# single_supply_control_V13_SD4.net
KiCad netlist of a schematic drawn in EAGLE
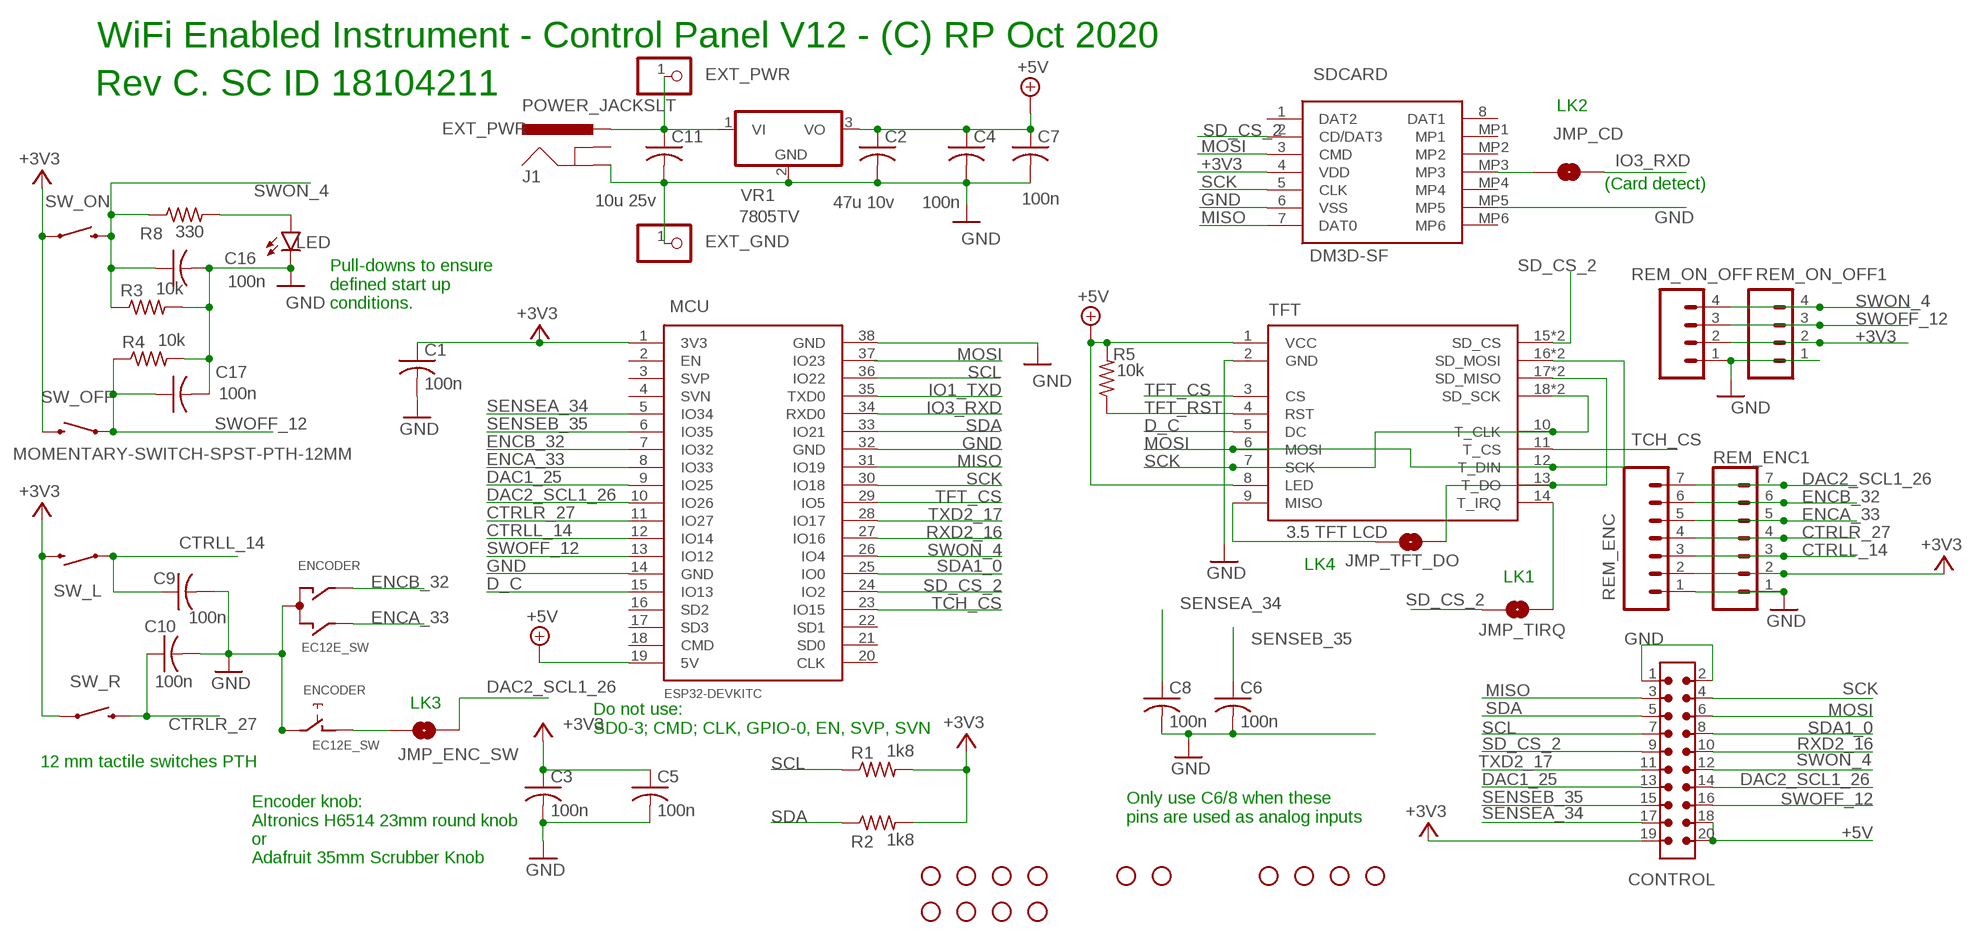
[diagram p0: schematic, sheet 1]

(export (version "E")
  (design (tool "Eeschema 10.0.6"))
  (components
    (comp (ref "C1")
      (value "100n")
      (footprint "eagle-import:C0805K")
      (libsource (lib "eagle-import") (part "C-USC0805K"))
    )
    (comp (ref "C2")
      (value "47u 10v")
      (footprint "eagle-import:C1210K")
      (libsource (lib "eagle-import") (part "C-USC1210K"))
    )
    (comp (ref "C3")
      (value "100n")
      (footprint "eagle-import:C0805K")
      (libsource (lib "eagle-import") (part "C-USC0805K"))
    )
    (comp (ref "C4")
      (value "100n")
      (footprint "eagle-import:C0805K")
      (libsource (lib "eagle-import") (part "C-USC0805K"))
    )
    (comp (ref "C5")
      (value "100n")
      (footprint "eagle-import:C0805K")
      (libsource (lib "eagle-import") (part "C-USC0805K"))
    )
    (comp (ref "C6")
      (value "100n")
      (footprint "eagle-import:C0805K")
      (libsource (lib "eagle-import") (part "C-USC0805K"))
    )
    (comp (ref "C7")
      (value "100n")
      (footprint "eagle-import:C0805K")
      (libsource (lib "eagle-import") (part "C-USC0805K"))
    )
    (comp (ref "C8")
      (value "100n")
      (footprint "eagle-import:C0805K")
      (libsource (lib "eagle-import") (part "C-USC0805K"))
    )
    (comp (ref "C9")
      (value "100n")
      (footprint "eagle-import:C0805K")
      (libsource (lib "eagle-import") (part "C-USC0805K"))
    )
    (comp (ref "C10")
      (value "100n")
      (footprint "eagle-import:C0805K")
      (libsource (lib "eagle-import") (part "C-USC0805K"))
    )
    (comp (ref "C11")
      (value "10u 25v")
      (footprint "eagle-import:C1210K")
      (libsource (lib "eagle-import") (part "C-USC1210K"))
    )
    (comp (ref "C16")
      (value "100n")
      (footprint "eagle-import:C0805K")
      (libsource (lib "eagle-import") (part "C-USC0805K"))
    )
    (comp (ref "C17")
      (value "100n")
      (footprint "eagle-import:C0805K")
      (libsource (lib "eagle-import") (part "C-USC0805K"))
    )
    (comp (ref "CONTROL")
      (value "6120XX21621_61202021621")
      (footprint "eagle-import:61202021621")
      (libsource (lib "eagle-import") (part "6120XX21621_61202021621"))
    )
    (comp (ref "ENCODER")
      (value "EC12E_SW")
      (footprint "eagle-import:ALPS_EC12E_SW")
      (fields (field (name "MPN") "EC12E2424407"))
      (libsource (lib "eagle-import") (part "EC12E_SW"))
    )
    (comp (ref "EXT_GND")
      (value "PINHD-1X1")
      (footprint "eagle-import:1X01")
      (libsource (lib "eagle-import") (part "PINHD-1X1"))
    )
    (comp (ref "EXT_PWR")
      (value "PINHD-1X1")
      (footprint "eagle-import:1X01")
      (libsource (lib "eagle-import") (part "PINHD-1X1"))
    )
    (comp (ref "H1")
      (value "STAND-OFF")
      (footprint "eagle-import:STAND-OFF")
      (libsource (lib "eagle-import") (part "STAND-OFF"))
    )
    (comp (ref "H2")
      (value "STAND-OFF")
      (footprint "eagle-import:STAND-OFF")
      (libsource (lib "eagle-import") (part "STAND-OFF"))
    )
    (comp (ref "H3")
      (value "STAND-OFF")
      (footprint "eagle-import:STAND-OFF")
      (libsource (lib "eagle-import") (part "STAND-OFF"))
    )
    (comp (ref "H4")
      (value "STAND-OFF")
      (footprint "eagle-import:STAND-OFF")
      (libsource (lib "eagle-import") (part "STAND-OFF"))
    )
    (comp (ref "H5")
      (value "STAND-OFF")
      (footprint "eagle-import:STAND-OFF")
      (libsource (lib "eagle-import") (part "STAND-OFF"))
    )
    (comp (ref "H6")
      (value "STAND-OFF")
      (footprint "eagle-import:STAND-OFF")
      (libsource (lib "eagle-import") (part "STAND-OFF"))
    )
    (comp (ref "H7")
      (value "STAND-OFF")
      (footprint "eagle-import:STAND-OFF")
      (libsource (lib "eagle-import") (part "STAND-OFF"))
    )
    (comp (ref "H8")
      (value "STAND-OFF")
      (footprint "eagle-import:STAND-OFF")
      (libsource (lib "eagle-import") (part "STAND-OFF"))
    )
    (comp (ref "H9")
      (value "STAND-OFF")
      (footprint "eagle-import:STAND-OFF")
      (libsource (lib "eagle-import") (part "STAND-OFF"))
    )
    (comp (ref "H10")
      (value "STAND-OFF")
      (footprint "eagle-import:STAND-OFF")
      (libsource (lib "eagle-import") (part "STAND-OFF"))
    )
    (comp (ref "H11")
      (value "STAND-OFF")
      (footprint "eagle-import:STAND-OFF")
      (libsource (lib "eagle-import") (part "STAND-OFF"))
    )
    (comp (ref "H12")
      (value "STAND-OFF")
      (footprint "eagle-import:STAND-OFF")
      (libsource (lib "eagle-import") (part "STAND-OFF"))
    )
    (comp (ref "H13")
      (value "STAND-OFF")
      (footprint "eagle-import:STAND-OFF")
      (libsource (lib "eagle-import") (part "STAND-OFF"))
    )
    (comp (ref "H14")
      (value "STAND-OFF")
      (footprint "eagle-import:STAND-OFF")
      (libsource (lib "eagle-import") (part "STAND-OFF"))
    )
    (comp (ref "J1")
      (value "POWER_JACKSLT")
      (footprint "eagle-import:POWER_JACK_SLOT")
      (libsource (lib "eagle-import") (part "POWER_JACKSLT"))
    )
    (comp (ref "JMP_CD")
      (value "JUMPER-SMT_2_NO_SILK")
      (footprint "eagle-import:SMT-JUMPER_2_NO_SILK")
      (libsource (lib "eagle-import") (part "JUMPER-SMT_2_NO_SILK"))
    )
    (comp (ref "JMP_ENC_SW")
      (value "JUMPER-SMT_2_NO_SILK")
      (footprint "eagle-import:SMT-JUMPER_2_NO_SILK")
      (libsource (lib "eagle-import") (part "JUMPER-SMT_2_NO_SILK"))
    )
    (comp (ref "JMP_TFT_DO")
      (value "JUMPER-SMT_2_NO_SILK")
      (footprint "eagle-import:SMT-JUMPER_2_NO_SILK")
      (libsource (lib "eagle-import") (part "JUMPER-SMT_2_NO_SILK"))
    )
    (comp (ref "JMP_TIRQ")
      (value "JUMPER-SMT_2_NO_SILK")
      (footprint "eagle-import:SMT-JUMPER_2_NO_SILK")
      (libsource (lib "eagle-import") (part "JUMPER-SMT_2_NO_SILK"))
    )
    (comp (ref "LED")
      (value "LED3MM")
      (footprint "eagle-import:LED_3MM")
      (libsource (lib "eagle-import") (part "LED3MM"))
    )
    (comp (ref "MCU")
      (value "ESP32DEVKITC")
      (footprint "eagle-import:ESP32-DEVKITC")
      (libsource (lib "eagle-import") (part "ESP32DEVKITC"))
    )
    (comp (ref "R1")
      (value "1k8")
      (footprint "eagle-import:R0805W")
      (libsource (lib "eagle-import") (part "R-US_R0805W"))
    )
    (comp (ref "R2")
      (value "1k8")
      (footprint "eagle-import:R0805W")
      (libsource (lib "eagle-import") (part "R-US_R0805W"))
    )
    (comp (ref "R3")
      (value "10k")
      (footprint "eagle-import:R0805W")
      (libsource (lib "eagle-import") (part "R-US_R0805W"))
    )
    (comp (ref "R4")
      (value "10k")
      (footprint "eagle-import:R0805W")
      (libsource (lib "eagle-import") (part "R-US_R0805W"))
    )
    (comp (ref "R5")
      (value "10k")
      (footprint "eagle-import:R0805W")
      (libsource (lib "eagle-import") (part "R-US_R0805W"))
    )
    (comp (ref "R8")
      (value "330")
      (footprint "eagle-import:R0805W")
      (libsource (lib "eagle-import") (part "R-US_R0805W"))
    )
    (comp (ref "REM_ENC")
      (value "CONN_07")
      (footprint "eagle-import:1X07")
      (libsource (lib "eagle-import") (part "CONN_07"))
    )
    (comp (ref "REM_ENC1")
      (value "CONN_07")
      (footprint "eagle-import:1X07")
      (libsource (lib "eagle-import") (part "CONN_07"))
    )
    (comp (ref "REM_ON_OFF")
      (value "CONN_04")
      (footprint "eagle-import:1X04")
      (libsource (lib "eagle-import") (part "CONN_04"))
    )
    (comp (ref "REM_ON_OFF1")
      (value "CONN_04")
      (footprint "eagle-import:1X04")
      (libsource (lib "eagle-import") (part "CONN_04"))
    )
    (comp (ref "SDCARD")
      (value "DM3D-SF")
      (footprint "eagle-import:DM3DSF")
      (fields (field (name "MOUSER_PART_NUMBER") "798-DM3D-SF"))
      (libsource (lib "eagle-import") (part "DM3D-SF"))
    )
    (comp (ref "SW_L")
      (value "MOMENTARY-SWITCH-SPST-PTH-12MM")
      (footprint "eagle-import:TACTILE_SWITCH_PTH_12MM")
      (libsource (lib "eagle-import") (part "MOMENTARY-SWITCH-SPST-PTH-12MM"))
    )
    (comp (ref "SW_OFF")
      (value "MOMENTARY-SWITCH-SPST-PTH-12MM")
      (footprint "eagle-import:TACTILE_SWITCH_PTH_12MM")
      (libsource (lib "eagle-import") (part "MOMENTARY-SWITCH-SPST-PTH-12MM"))
    )
    (comp (ref "SW_ON")
      (value "MOMENTARY-SWITCH-SPST-PTH-12MM")
      (footprint "eagle-import:TACTILE_SWITCH_PTH_12MM")
      (libsource (lib "eagle-import") (part "MOMENTARY-SWITCH-SPST-PTH-12MM"))
    )
    (comp (ref "SW_R")
      (value "MOMENTARY-SWITCH-SPST-PTH-12MM")
      (footprint "eagle-import:TACTILE_SWITCH_PTH_12MM")
      (libsource (lib "eagle-import") (part "MOMENTARY-SWITCH-SPST-PTH-12MM"))
    )
    (comp (ref "TFT")
      (value "2.8_3.5_TFT_TOUCH")
      (footprint "eagle-import:2.8_3.5_TFT_LCD")
      (libsource (lib "eagle-import") (part "2.8_3.5_TFT_TOUCH"))
    )
    (comp (ref "VR1")
      (value "7805TV")
      (footprint "eagle-import:TO220V")
      (libsource (lib "eagle-import") (part "78TV05"))
    )
  )
  (nets
    (net (code "1") (name "+3V3") (class "Default")
      (node (ref "C1") (pin "1") (pinfunction "1_1") (pintype "passive"))
      (node (ref "C3") (pin "1") (pinfunction "1_1") (pintype "passive"))
      (node (ref "C5") (pin "1") (pinfunction "1_1") (pintype "passive"))
      (node (ref "CONTROL") (pin "19") (pinfunction "19_19") (pintype "passive"))
      (node (ref "MCU") (pin "1") (pinfunction "3V3_1") (pintype "bidirectional"))
      (node (ref "R1") (pin "2") (pinfunction "2_2") (pintype "passive"))
      (node (ref "R2") (pin "2") (pinfunction "2_2") (pintype "passive"))
      (node (ref "REM_ENC") (pin "2") (pinfunction "2_2") (pintype "passive"))
      (node (ref "REM_ENC1") (pin "2") (pinfunction "2_2") (pintype "passive"))
      (node (ref "REM_ON_OFF") (pin "2") (pinfunction "2_2") (pintype "passive"))
      (node (ref "REM_ON_OFF1") (pin "2") (pinfunction "2_2") (pintype "passive"))
      (node (ref "SDCARD") (pin "4") (pinfunction "VDD_4") (pintype "bidirectional"))
      (node (ref "SW_L") (pin "3") (pinfunction "2_3") (pintype "passive"))
      (node (ref "SW_OFF") (pin "3") (pinfunction "2_3") (pintype "passive"))
      (node (ref "SW_ON") (pin "1") (pinfunction "1_1") (pintype "passive"))
      (node (ref "SW_R") (pin "1") (pinfunction "1_1") (pintype "passive"))
    )
    (net (code "2") (name "+5V") (class "Default")
      (node (ref "C2") (pin "1") (pinfunction "1_1") (pintype "passive"))
      (node (ref "C4") (pin "1") (pinfunction "1_1") (pintype "passive"))
      (node (ref "C7") (pin "1") (pinfunction "1_1") (pintype "passive"))
      (node (ref "CONTROL") (pin "18") (pinfunction "18_18") (pintype "passive"))
      (node (ref "CONTROL") (pin "20") (pinfunction "20_20") (pintype "passive"))
      (node (ref "MCU") (pin "19") (pinfunction "5V_19") (pintype "bidirectional"))
      (node (ref "R5") (pin "2") (pinfunction "2_2") (pintype "passive"))
      (node (ref "TFT") (pin "1") (pinfunction "VCC_1") (pintype "power_in"))
      (node (ref "TFT") (pin "8") (pinfunction "LED_8") (pintype "bidirectional"))
      (node (ref "VR1") (pin "3") (pinfunction "VO_3") (pintype "passive"))
    )
    (net (code "3") (name "/CTRLL_14") (class "Default")
      (node (ref "C9") (pin "1") (pinfunction "1_1") (pintype "passive"))
      (node (ref "MCU") (pin "12") (pinfunction "IO14_12") (pintype "bidirectional"))
      (node (ref "REM_ENC") (pin "3") (pinfunction "3_3") (pintype "passive"))
      (node (ref "REM_ENC1") (pin "3") (pinfunction "3_3") (pintype "passive"))
      (node (ref "SW_L") (pin "1") (pinfunction "1_1") (pintype "passive"))
    )
    (net (code "4") (name "/CTRLR_27") (class "Default")
      (node (ref "C10") (pin "1") (pinfunction "1_1") (pintype "passive"))
      (node (ref "MCU") (pin "11") (pinfunction "IO27_11") (pintype "bidirectional"))
      (node (ref "REM_ENC") (pin "4") (pinfunction "4_4") (pintype "passive"))
      (node (ref "REM_ENC1") (pin "4") (pinfunction "4_4") (pintype "passive"))
      (node (ref "SW_R") (pin "3") (pinfunction "2_3") (pintype "passive"))
    )
    (net (code "5") (name "/DAC1_25") (class "Default")
      (node (ref "CONTROL") (pin "13") (pinfunction "13_13") (pintype "passive"))
      (node (ref "MCU") (pin "9") (pinfunction "IO25_9") (pintype "bidirectional"))
    )
    (net (code "6") (name "/DAC2_SCL1_26") (class "Default")
      (node (ref "CONTROL") (pin "14") (pinfunction "14_14") (pintype "passive"))
      (node (ref "JMP_ENC_SW") (pin "2") (pinfunction "2_2") (pintype "passive"))
      (node (ref "MCU") (pin "10") (pinfunction "IO26_10") (pintype "bidirectional"))
      (node (ref "REM_ENC") (pin "7") (pinfunction "7_7") (pintype "passive"))
      (node (ref "REM_ENC1") (pin "7") (pinfunction "7_7") (pintype "passive"))
    )
    (net (code "7") (name "/D_C") (class "Default")
      (node (ref "MCU") (pin "15") (pinfunction "IO13_15") (pintype "bidirectional"))
      (node (ref "TFT") (pin "5") (pinfunction "DC_5") (pintype "bidirectional"))
    )
    (net (code "8") (name "/ENCA_33") (class "Default")
      (node (ref "ENCODER") (pin "B") (pinfunction "B_B") (pintype "passive"))
      (node (ref "MCU") (pin "8") (pinfunction "IO33_8") (pintype "bidirectional"))
      (node (ref "REM_ENC") (pin "5") (pinfunction "5_5") (pintype "passive"))
      (node (ref "REM_ENC1") (pin "5") (pinfunction "5_5") (pintype "passive"))
    )
    (net (code "9") (name "/ENCB_32") (class "Default")
      (node (ref "ENCODER") (pin "A") (pinfunction "A_A") (pintype "passive"))
      (node (ref "MCU") (pin "7") (pinfunction "IO32_7") (pintype "bidirectional"))
      (node (ref "REM_ENC") (pin "6") (pinfunction "6_6") (pintype "passive"))
      (node (ref "REM_ENC1") (pin "6") (pinfunction "6_6") (pintype "passive"))
    )
    (net (code "10") (name "/EXT_PWR") (class "Default")
      (node (ref "C11") (pin "1") (pinfunction "1_1") (pintype "passive"))
      (node (ref "EXT_PWR") (pin "1") (pinfunction "1_1") (pintype "passive"))
      (node (ref "J1") (pin "PWR") (pinfunction "PWR_PWR") (pintype "bidirectional"))
      (node (ref "VR1") (pin "1") (pinfunction "VI_1") (pintype "input"))
    )
    (net (code "11") (name "/IO1_TXD") (class "Default")
      (node (ref "MCU") (pin "35") (pinfunction "TXD0_35") (pintype "bidirectional"))
    )
    (net (code "12") (name "/IO3_RXD") (class "Default")
      (node (ref "JMP_CD") (pin "2") (pinfunction "2_2") (pintype "passive"))
      (node (ref "MCU") (pin "34") (pinfunction "RXD0_34") (pintype "bidirectional"))
    )
    (net (code "13") (name "/MISO") (class "Default")
      (node (ref "CONTROL") (pin "3") (pinfunction "3_3") (pintype "passive"))
      (node (ref "JMP_TFT_DO") (pin "2") (pinfunction "2_2") (pintype "passive"))
      (node (ref "MCU") (pin "31") (pinfunction "IO19_31") (pintype "bidirectional"))
      (node (ref "SDCARD") (pin "7") (pinfunction "DAT0_7") (pintype "bidirectional"))
      (node (ref "TFT") (pin "13") (pinfunction "T_DO_13") (pintype "bidirectional"))
      (node (ref "TFT") (pin "17") (pinfunction "SD_MISO_17") (pintype "bidirectional"))
      (node (ref "TFT") (pin "30") (pinfunction "SD_MISO_30") (pintype "bidirectional"))
    )
    (net (code "14") (name "/MOSI") (class "Default")
      (node (ref "CONTROL") (pin "6") (pinfunction "6_6") (pintype "passive"))
      (node (ref "MCU") (pin "37") (pinfunction "IO23_37") (pintype "bidirectional"))
      (node (ref "SDCARD") (pin "3") (pinfunction "CMD_3") (pintype "bidirectional"))
      (node (ref "TFT") (pin "12") (pinfunction "T_DIN_12") (pintype "bidirectional"))
      (node (ref "TFT") (pin "16") (pinfunction "SD_MOSI_16") (pintype "bidirectional"))
      (node (ref "TFT") (pin "29") (pinfunction "SD_MOSI_29") (pintype "bidirectional"))
      (node (ref "TFT") (pin "6") (pinfunction "MOSI_6") (pintype "bidirectional"))
    )
    (net (code "15") (name "/RXD2_16") (class "Default")
      (node (ref "CONTROL") (pin "10") (pinfunction "10_10") (pintype "passive"))
      (node (ref "MCU") (pin "27") (pinfunction "IO16_27") (pintype "bidirectional"))
    )
    (net (code "16") (name "/SCK") (class "Default")
      (node (ref "CONTROL") (pin "4") (pinfunction "4_4") (pintype "passive"))
      (node (ref "MCU") (pin "30") (pinfunction "IO18_30") (pintype "bidirectional"))
      (node (ref "SDCARD") (pin "5") (pinfunction "CLK_5") (pintype "bidirectional"))
      (node (ref "TFT") (pin "10") (pinfunction "T_CLK_10") (pintype "bidirectional"))
      (node (ref "TFT") (pin "18") (pinfunction "SD_SCK_18") (pintype "bidirectional"))
      (node (ref "TFT") (pin "31") (pinfunction "SD_SCK_31") (pintype "bidirectional"))
      (node (ref "TFT") (pin "7") (pinfunction "SCK_7") (pintype "bidirectional"))
    )
    (net (code "17") (name "/SCL") (class "Default")
      (node (ref "CONTROL") (pin "7") (pinfunction "7_7") (pintype "passive"))
      (node (ref "MCU") (pin "36") (pinfunction "IO22_36") (pintype "bidirectional"))
      (node (ref "R1") (pin "1") (pinfunction "1_1") (pintype "passive"))
    )
    (net (code "18") (name "/SDA") (class "Default")
      (node (ref "CONTROL") (pin "5") (pinfunction "5_5") (pintype "passive"))
      (node (ref "MCU") (pin "33") (pinfunction "IO21_33") (pintype "bidirectional"))
      (node (ref "R2") (pin "1") (pinfunction "1_1") (pintype "passive"))
    )
    (net (code "19") (name "/SDA1_0") (class "Default")
      (node (ref "CONTROL") (pin "8") (pinfunction "8_8") (pintype "passive"))
      (node (ref "MCU") (pin "25") (pinfunction "IO0_25") (pintype "bidirectional"))
    )
    (net (code "20") (name "/SD_CS_2") (class "Default")
      (node (ref "CONTROL") (pin "9") (pinfunction "9_9") (pintype "passive"))
      (node (ref "JMP_TIRQ") (pin "1") (pinfunction "1_1") (pintype "passive"))
      (node (ref "MCU") (pin "24") (pinfunction "IO2_24") (pintype "bidirectional"))
      (node (ref "SDCARD") (pin "2") (pinfunction "CD/DAT3_2") (pintype "bidirectional"))
      (node (ref "TFT") (pin "15") (pinfunction "SD_CS_15") (pintype "bidirectional"))
      (node (ref "TFT") (pin "28") (pinfunction "SD_CS_28") (pintype "bidirectional"))
    )
    (net (code "21") (name "/SENSEA_34") (class "Default")
      (node (ref "C8") (pin "1") (pinfunction "1_1") (pintype "passive"))
      (node (ref "CONTROL") (pin "17") (pinfunction "17_17") (pintype "passive"))
      (node (ref "MCU") (pin "5") (pinfunction "IO34_5") (pintype "bidirectional"))
    )
    (net (code "22") (name "/SENSEB_35") (class "Default")
      (node (ref "C6") (pin "1") (pinfunction "1_1") (pintype "passive"))
      (node (ref "CONTROL") (pin "15") (pinfunction "15_15") (pintype "passive"))
      (node (ref "MCU") (pin "6") (pinfunction "IO35_6") (pintype "bidirectional"))
    )
    (net (code "23") (name "/SWOFF_12") (class "Default")
      (node (ref "C17") (pin "1") (pinfunction "1_1") (pintype "passive"))
      (node (ref "CONTROL") (pin "16") (pinfunction "16_16") (pintype "passive"))
      (node (ref "MCU") (pin "13") (pinfunction "IO12_13") (pintype "bidirectional"))
      (node (ref "R4") (pin "1") (pinfunction "1_1") (pintype "passive"))
      (node (ref "REM_ON_OFF") (pin "3") (pinfunction "3_3") (pintype "passive"))
      (node (ref "REM_ON_OFF1") (pin "3") (pinfunction "3_3") (pintype "passive"))
      (node (ref "SW_OFF") (pin "1") (pinfunction "1_1") (pintype "passive"))
    )
    (net (code "24") (name "/SWON_4") (class "Default")
      (node (ref "C16") (pin "1") (pinfunction "1_1") (pintype "passive"))
      (node (ref "CONTROL") (pin "12") (pinfunction "12_12") (pintype "passive"))
      (node (ref "MCU") (pin "26") (pinfunction "IO4_26") (pintype "bidirectional"))
      (node (ref "R3") (pin "1") (pinfunction "1_1") (pintype "passive"))
      (node (ref "R8") (pin "1") (pinfunction "1_1") (pintype "passive"))
      (node (ref "REM_ON_OFF") (pin "4") (pinfunction "4_4") (pintype "passive"))
      (node (ref "REM_ON_OFF1") (pin "4") (pinfunction "4_4") (pintype "passive"))
      (node (ref "SW_ON") (pin "3") (pinfunction "2_3") (pintype "passive"))
    )
    (net (code "25") (name "/TCH_CS") (class "Default")
      (node (ref "MCU") (pin "23") (pinfunction "IO15_23") (pintype "bidirectional"))
      (node (ref "TFT") (pin "11") (pinfunction "T_CS_11") (pintype "bidirectional"))
    )
    (net (code "26") (name "/TFT_CS") (class "Default")
      (node (ref "MCU") (pin "29") (pinfunction "IO5_29") (pintype "bidirectional"))
      (node (ref "TFT") (pin "3") (pinfunction "CS_3") (pintype "bidirectional"))
    )
    (net (code "27") (name "/TFT_RST") (class "Default")
      (node (ref "R5") (pin "1") (pinfunction "1_1") (pintype "passive"))
      (node (ref "TFT") (pin "4") (pinfunction "RST_4") (pintype "bidirectional"))
    )
    (net (code "28") (name "/TXD2_17") (class "Default")
      (node (ref "CONTROL") (pin "11") (pinfunction "11_11") (pintype "passive"))
      (node (ref "MCU") (pin "28") (pinfunction "IO17_28") (pintype "bidirectional"))
    )
    (net (code "29") (name "GND") (class "Default")
      (node (ref "C1") (pin "2") (pinfunction "2_2") (pintype "passive"))
      (node (ref "C10") (pin "2") (pinfunction "2_2") (pintype "passive"))
      (node (ref "C11") (pin "2") (pinfunction "2_2") (pintype "passive"))
      (node (ref "C16") (pin "2") (pinfunction "2_2") (pintype "passive"))
      (node (ref "C17") (pin "2") (pinfunction "2_2") (pintype "passive"))
      (node (ref "C2") (pin "2") (pinfunction "2_2") (pintype "passive"))
      (node (ref "C3") (pin "2") (pinfunction "2_2") (pintype "passive"))
      (node (ref "C4") (pin "2") (pinfunction "2_2") (pintype "passive"))
      (node (ref "C5") (pin "2") (pinfunction "2_2") (pintype "passive"))
      (node (ref "C6") (pin "2") (pinfunction "2_2") (pintype "passive"))
      (node (ref "C7") (pin "2") (pinfunction "2_2") (pintype "passive"))
      (node (ref "C8") (pin "2") (pinfunction "2_2") (pintype "passive"))
      (node (ref "C9") (pin "2") (pinfunction "2_2") (pintype "passive"))
      (node (ref "CONTROL") (pin "1") (pinfunction "1_1") (pintype "passive"))
      (node (ref "CONTROL") (pin "2") (pinfunction "2_2") (pintype "passive"))
      (node (ref "ENCODER") (pin "C") (pinfunction "C_C") (pintype "passive"))
      (node (ref "ENCODER") (pin "E") (pinfunction "2_E") (pintype "passive"))
      (node (ref "EXT_GND") (pin "1") (pinfunction "1_1") (pintype "passive"))
      (node (ref "J1") (pin "GND@2") (pinfunction "GND_GND@2") (pintype "bidirectional"))
      (node (ref "LED") (pin "K") (pinfunction "C_K") (pintype "passive"))
      (node (ref "MCU") (pin "14") (pinfunction "GND_14") (pintype "bidirectional"))
      (node (ref "MCU") (pin "32") (pinfunction "GND_32") (pintype "bidirectional"))
      (node (ref "MCU") (pin "38") (pinfunction "GND_38") (pintype "bidirectional"))
      (node (ref "R3") (pin "2") (pinfunction "2_2") (pintype "passive"))
      (node (ref "R4") (pin "2") (pinfunction "2_2") (pintype "passive"))
      (node (ref "REM_ENC") (pin "1") (pinfunction "1_1") (pintype "passive"))
      (node (ref "REM_ENC1") (pin "1") (pinfunction "1_1") (pintype "passive"))
      (node (ref "REM_ON_OFF") (pin "1") (pinfunction "1_1") (pintype "passive"))
      (node (ref "REM_ON_OFF1") (pin "1") (pinfunction "1_1") (pintype "passive"))
      (node (ref "SDCARD") (pin "6") (pinfunction "VSS_6") (pintype "bidirectional"))
      (node (ref "SDCARD") (pin "MP5") (pinfunction "MP5_MP5") (pintype "bidirectional"))
      (node (ref "TFT") (pin "2") (pinfunction "GND_2") (pintype "power_in"))
      (node (ref "VR1") (pin "2") (pinfunction "GND_2") (pintype "passive"))
    )
    (net (code "30") (name "Net-(ENCODERB-1)") (class "Default")
      (node (ref "ENCODER") (pin "D") (pinfunction "1_D") (pintype "passive"))
      (node (ref "JMP_ENC_SW") (pin "1") (pinfunction "1_1") (pintype "passive"))
    )
    (net (code "31") (name "Net-(JMP_CD-Pad1)") (class "Default")
      (node (ref "JMP_CD") (pin "1") (pinfunction "1_1") (pintype "passive"))
      (node (ref "SDCARD") (pin "MP3") (pinfunction "MP3_MP3") (pintype "bidirectional"))
    )
    (net (code "32") (name "Net-(LED-PadA)") (class "Default")
      (node (ref "LED") (pin "A") (pinfunction "A_A") (pintype "passive"))
      (node (ref "R8") (pin "2") (pinfunction "2_2") (pintype "passive"))
    )
    (net (code "33") (name "Net-(TFT-MISO)") (class "Default")
      (node (ref "JMP_TFT_DO") (pin "1") (pinfunction "1_1") (pintype "passive"))
      (node (ref "TFT") (pin "9") (pinfunction "MISO_9") (pintype "bidirectional"))
    )
    (net (code "34") (name "Net-(TFT-T_IRQ)") (class "Default")
      (node (ref "JMP_TIRQ") (pin "2") (pinfunction "2_2") (pintype "passive"))
      (node (ref "TFT") (pin "14") (pinfunction "T_IRQ_14") (pintype "bidirectional"))
    )
    (net (code "35") (name "unconnected-(J1-GNDBREAK-PadGND@1)") (class "Default")
      (node (ref "J1") (pin "GND@1") (pinfunction "GNDBREAK_GND@1") (pintype "bidirectional"))
    )
    (net (code "36") (name "unconnected-(MCU-CLK-Pad20)") (class "Default")
      (node (ref "MCU") (pin "20") (pinfunction "CLK_20") (pintype "bidirectional"))
    )
    (net (code "37") (name "unconnected-(MCU-CMD-Pad18)") (class "Default")
      (node (ref "MCU") (pin "18") (pinfunction "CMD_18") (pintype "bidirectional"))
    )
    (net (code "38") (name "unconnected-(MCU-EN-Pad2)") (class "Default")
      (node (ref "MCU") (pin "2") (pinfunction "EN_2") (pintype "bidirectional"))
    )
    (net (code "39") (name "unconnected-(MCU-SD0-Pad21)") (class "Default")
      (node (ref "MCU") (pin "21") (pinfunction "SD0_21") (pintype "bidirectional"))
    )
    (net (code "40") (name "unconnected-(MCU-SD1-Pad22)") (class "Default")
      (node (ref "MCU") (pin "22") (pinfunction "SD1_22") (pintype "bidirectional"))
    )
    (net (code "41") (name "unconnected-(MCU-SD2-Pad16)") (class "Default")
      (node (ref "MCU") (pin "16") (pinfunction "SD2_16") (pintype "bidirectional"))
    )
    (net (code "42") (name "unconnected-(MCU-SD3-Pad17)") (class "Default")
      (node (ref "MCU") (pin "17") (pinfunction "SD3_17") (pintype "bidirectional"))
    )
    (net (code "43") (name "unconnected-(MCU-SVN-Pad4)") (class "Default")
      (node (ref "MCU") (pin "4") (pinfunction "SVN_4") (pintype "bidirectional"))
    )
    (net (code "44") (name "unconnected-(MCU-SVP-Pad3)") (class "Default")
      (node (ref "MCU") (pin "3") (pinfunction "SVP_3") (pintype "bidirectional"))
    )
    (net (code "45") (name "unconnected-(SDCARD-DAT1-Pad8)") (class "Default")
      (node (ref "SDCARD") (pin "8") (pinfunction "DAT1_8") (pintype "bidirectional"))
    )
    (net (code "46") (name "unconnected-(SDCARD-DAT2-Pad1)") (class "Default")
      (node (ref "SDCARD") (pin "1") (pinfunction "DAT2_1") (pintype "bidirectional"))
    )
    (net (code "47") (name "unconnected-(SDCARD-PadMP1)") (class "Default")
      (node (ref "SDCARD") (pin "MP1") (pinfunction "MP1_MP1") (pintype "bidirectional"))
    )
    (net (code "48") (name "unconnected-(SDCARD-PadMP2)") (class "Default")
      (node (ref "SDCARD") (pin "MP2") (pinfunction "MP2_MP2") (pintype "bidirectional"))
    )
    (net (code "49") (name "unconnected-(SDCARD-PadMP4)") (class "Default")
      (node (ref "SDCARD") (pin "MP4") (pinfunction "MP4_MP4") (pintype "bidirectional"))
    )
    (net (code "50") (name "unconnected-(SDCARD-PadMP6)") (class "Default")
      (node (ref "SDCARD") (pin "MP6") (pinfunction "MP6_MP6") (pintype "bidirectional"))
    )
  )
)
